# 28pins_schematic.net
KiCad netlist of a schematic drawn in Altium Designer
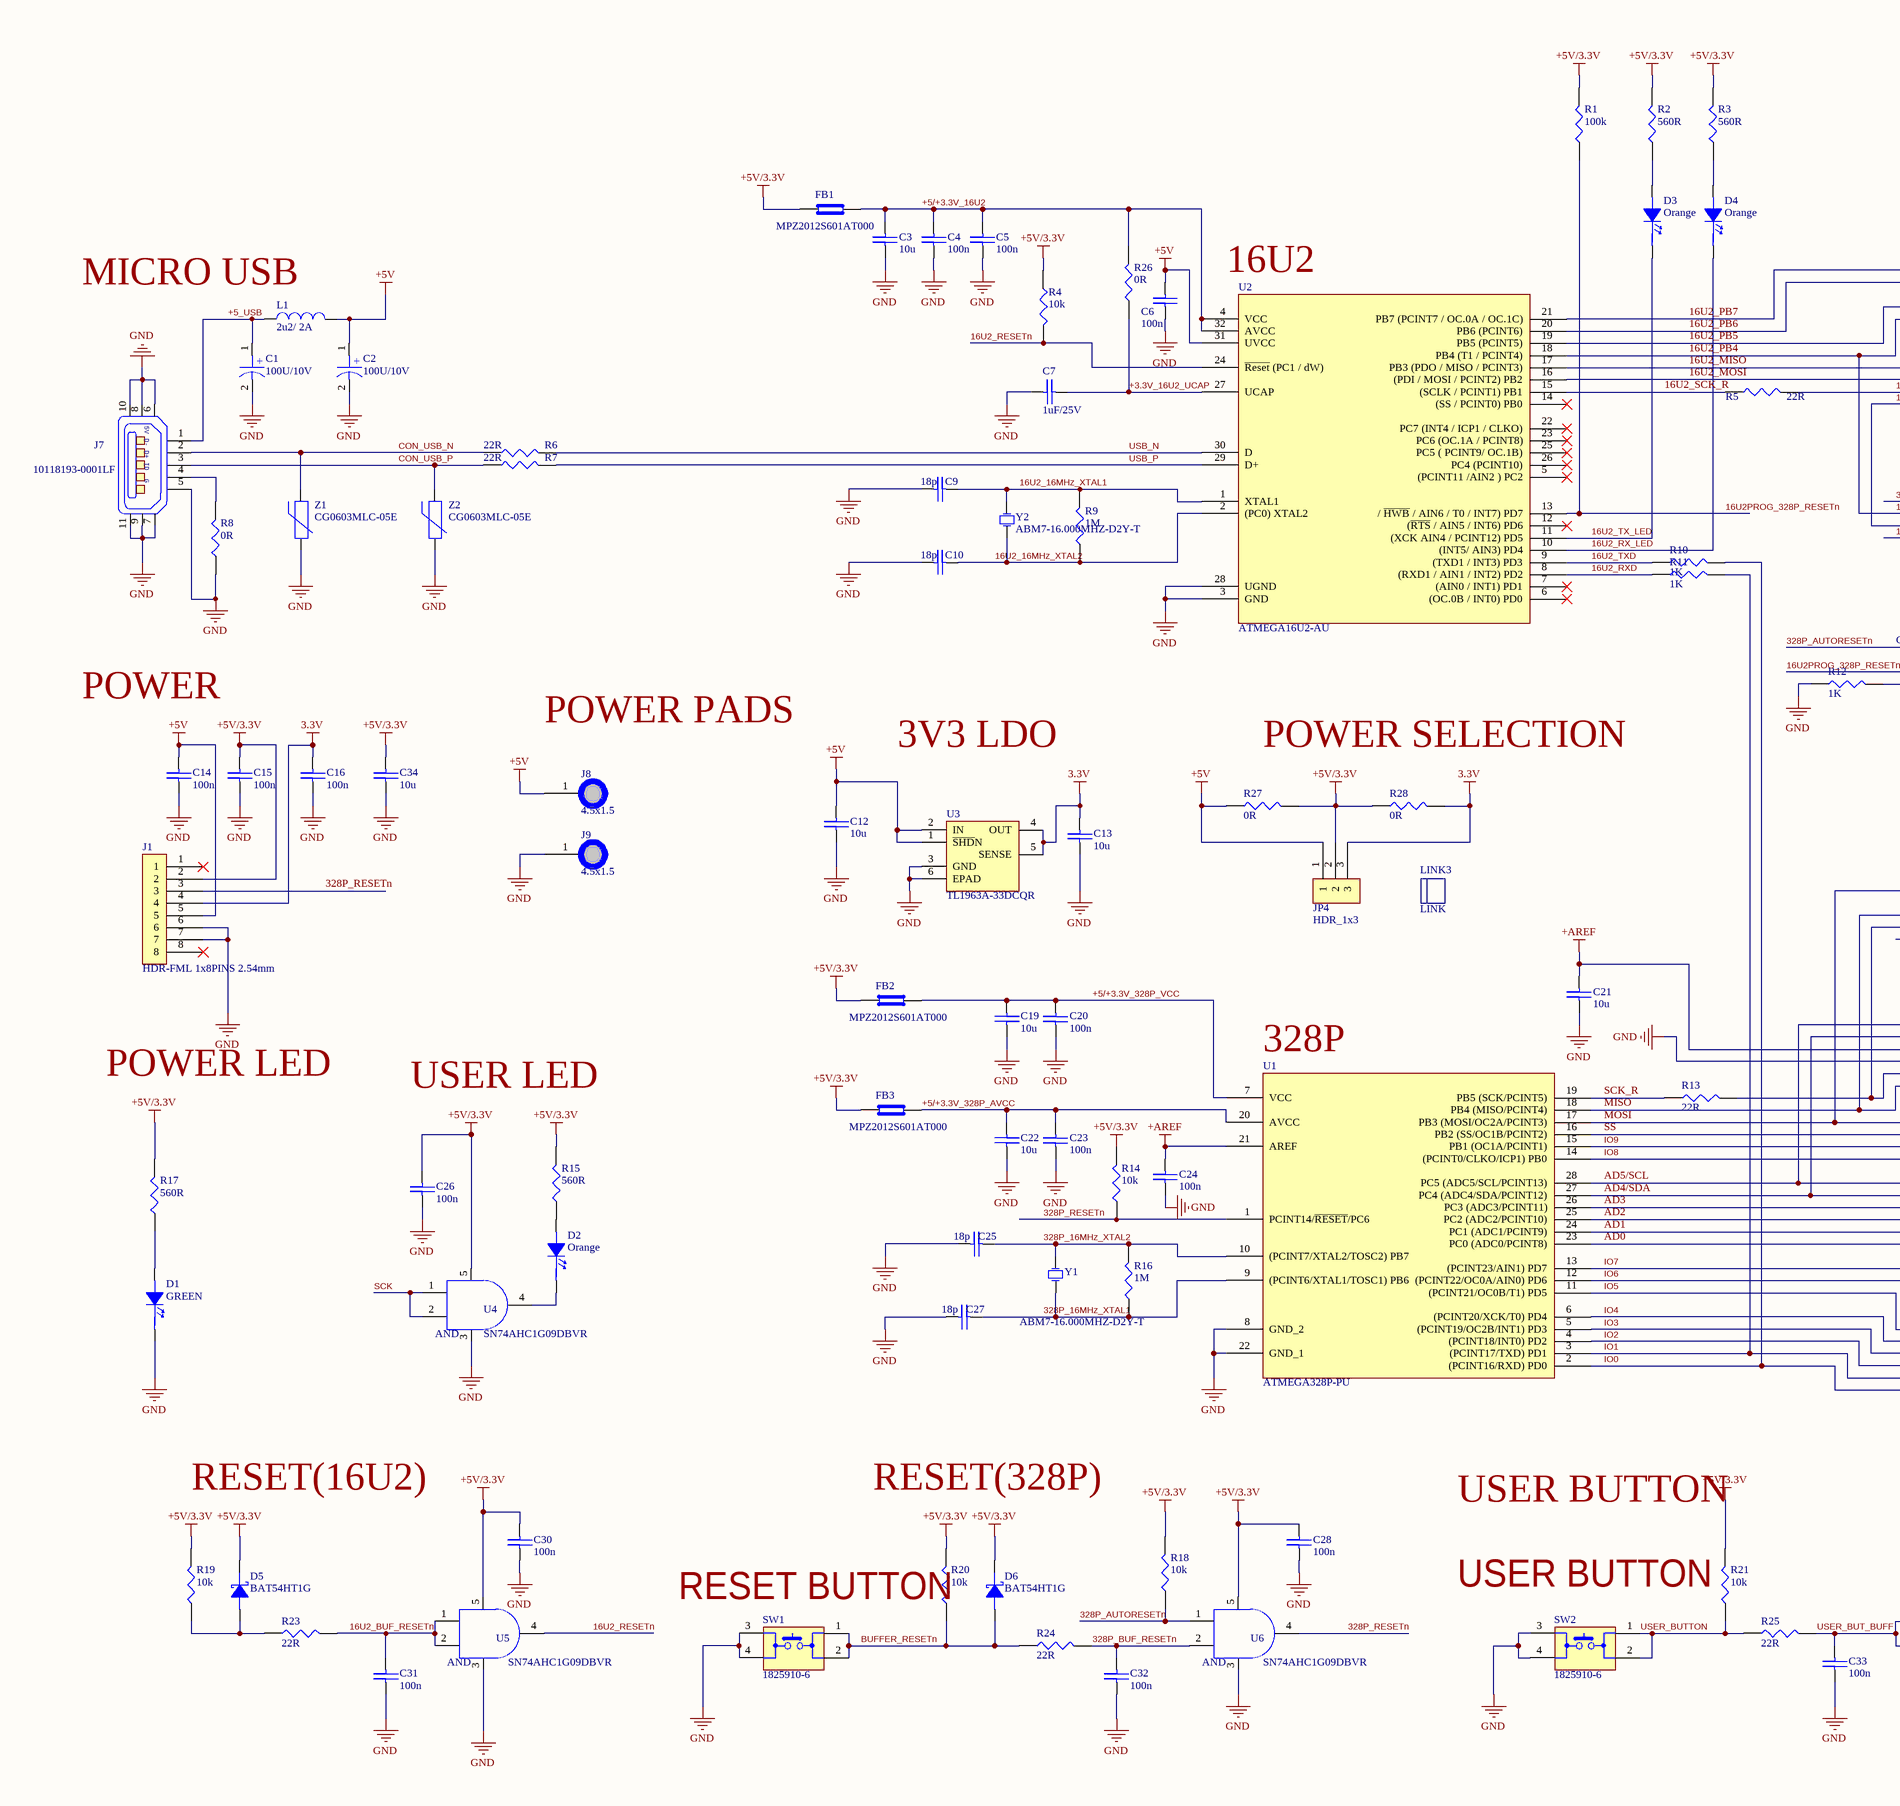
[diagram p0: 28pins_schematic.SchDoc, left]
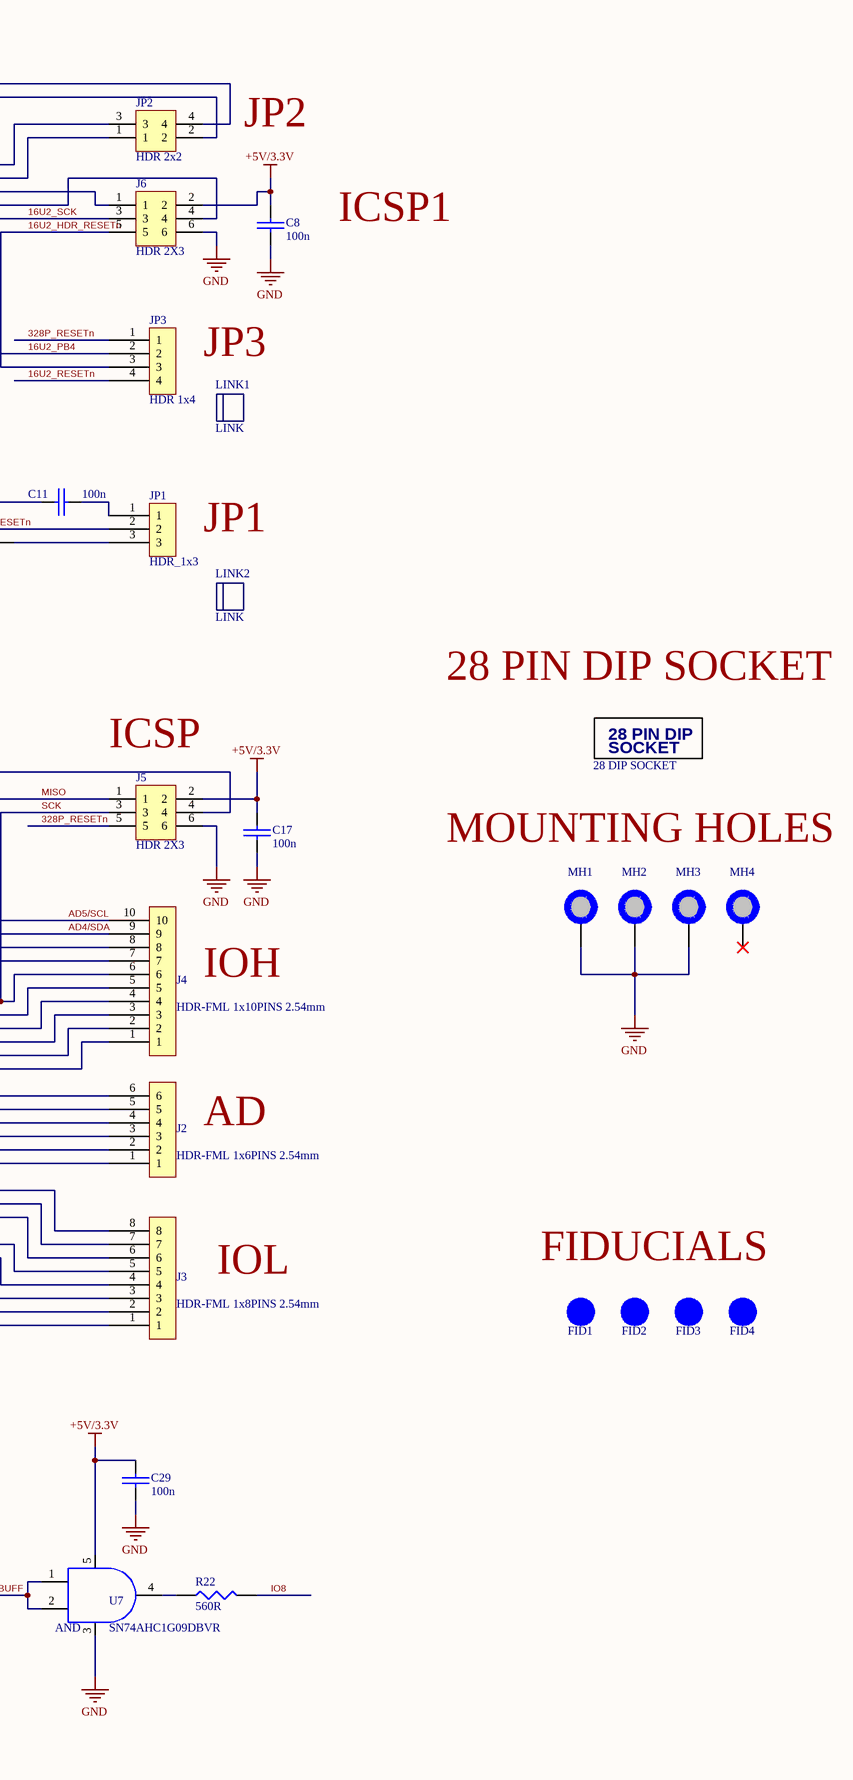
[diagram p1: 28pins_schematic.SchDoc, right]

(export (version "E")
  (design (tool "Eeschema 10.0.6"))
  (components
    (comp (ref "C1")
      (value "100U/10V")
      (footprint "C_ALU_CSIZE")
      (description "Cap Aluminum 100uF 10V 20% (5 X 5.4mm) SMD 50mA 1000 hr 85°C T/R")
      (fields
        (field (name "MANUFACTURER") "Panasonic")
        (field (name "MANUFACTURER PART NUMBER") "EEE-1AA101WR")
      )
      (libsource (lib "28pins_arduino_sch_lib") (part "EEE-1AA101WR"))
    )
    (comp (ref "C2")
      (value "100U/10V")
      (footprint "C_ALU_CSIZE")
      (description "Cap Aluminum 100uF 10V 20% (5 X 5.4mm) SMD 50mA 1000 hr 85°C T/R")
      (fields
        (field (name "MANUFACTURER") "Panasonic")
        (field (name "MANUFACTURER PART NUMBER") "EEE-1AA101WR")
      )
      (libsource (lib "28pins_arduino_sch_lib") (part "EEE-1AA101WR"))
    )
    (comp (ref "C3")
      (value "10u")
      (footprint "C0805 10u/16V")
      (description "Cap Ceramic 22uF 16V X5R 20% SMD 0805 85C Plastic T/R")
      (fields
        (field (name "MANUFACTURER") "TDK")
        (field (name "MANUFACTURER PART NUMBER") "C2012X5R1C226M125AC")
      )
      (libsource (lib "28pins_arduino_sch_lib") (part "C2012X5R1C226M125AC"))
    )
    (comp (ref "C4")
      (value "100n")
      (footprint "C0805")
      (fields
        (field (name "MANUFACTURER") "TDK")
        (field (name "MANUFACTURER PART NUMBER") "C2012X7R1H104K085AA")
        (field (name "TOLERANCE") "10%")
      )
      (libsource (lib "28pins_arduino_sch_lib") (part "C2012X7R1H104K085AA"))
    )
    (comp (ref "C5")
      (value "100n")
      (footprint "C0805")
      (fields
        (field (name "MANUFACTURER") "TDK")
        (field (name "MANUFACTURER PART NUMBER") "C2012X7R1H104K085AA")
        (field (name "TOLERANCE") "10%")
      )
      (libsource (lib "28pins_arduino_sch_lib") (part "C2012X7R1H104K085AA"))
    )
    (comp (ref "C6")
      (value "100n")
      (footprint "C0805")
      (fields
        (field (name "MANUFACTURER") "TDK")
        (field (name "MANUFACTURER PART NUMBER") "C2012X7R1H104K085AA")
        (field (name "TOLERANCE") "10%")
      )
      (libsource (lib "28pins_arduino_sch_lib") (part "C2012X7R1H104K085AA"))
    )
    (comp (ref "C7")
      (value "1uF/25V")
      (footprint "C0805")
      (fields
        (field (name "MANUFACTURER") "TDK")
        (field (name "MANUFACTURER PART NUMBER") "C2012X5R1E105K125AA")
        (field (name "TOLERANCE") "10%")
      )
      (libsource (lib "28pins_arduino_sch_lib") (part "C2012X5R1E105K125AA"))
    )
    (comp (ref "C8")
      (value "100n")
      (footprint "C0805")
      (fields
        (field (name "MANUFACTURER") "TDK")
        (field (name "MANUFACTURER PART NUMBER") "C2012X7R1H104K085AA")
        (field (name "TOLERANCE") "10%")
      )
      (libsource (lib "28pins_arduino_sch_lib") (part "C2012X7R1H104K085AA"))
    )
    (comp (ref "C9")
      (value "18p")
      (footprint "C0805")
      (description "CAP CER 18PF 50V C0G/NP0 0805")
      (fields
        (field (name "MANUFACTURER") "KEMET")
        (field (name "MANUFACTURER PART NUMBER") "C0805C180J5GACTU")
      )
      (libsource (lib "28pins_arduino_sch_lib") (part "C0805C180J5GACTU"))
    )
    (comp (ref "C10")
      (value "18p")
      (footprint "C0805")
      (description "CAP CER 18PF 50V C0G/NP0 0805")
      (fields
        (field (name "MANUFACTURER") "KEMET")
        (field (name "MANUFACTURER PART NUMBER") "C0805C180J5GACTU")
      )
      (libsource (lib "28pins_arduino_sch_lib") (part "C0805C180J5GACTU"))
    )
    (comp (ref "C11")
      (value "100n")
      (footprint "C0805")
      (fields
        (field (name "MANUFACTURER") "TDK")
        (field (name "MANUFACTURER PART NUMBER") "C2012X7R1H104K085AA")
        (field (name "TOLERANCE") "10%")
      )
      (libsource (lib "28pins_arduino_sch_lib") (part "C2012X7R1H104K085AA"))
    )
    (comp (ref "C12")
      (value "10u")
      (footprint "C0805 10u/16V")
      (description "Cap Ceramic 22uF 16V X5R 20% SMD 0805 85C Plastic T/R")
      (fields
        (field (name "MANUFACTURER") "TDK")
        (field (name "MANUFACTURER PART NUMBER") "C2012X5R1C226M125AC")
      )
      (libsource (lib "28pins_arduino_sch_lib") (part "C2012X5R1C226M125AC"))
    )
    (comp (ref "C13")
      (value "10u")
      (footprint "C0805 10u/16V")
      (description "Cap Ceramic 22uF 16V X5R 20% SMD 0805 85C Plastic T/R")
      (fields
        (field (name "MANUFACTURER") "TDK")
        (field (name "MANUFACTURER PART NUMBER") "C2012X5R1C226M125AC")
      )
      (libsource (lib "28pins_arduino_sch_lib") (part "C2012X5R1C226M125AC"))
    )
    (comp (ref "C14")
      (value "100n")
      (footprint "C0805")
      (fields
        (field (name "MANUFACTURER") "TDK")
        (field (name "MANUFACTURER PART NUMBER") "C2012X7R1H104K085AA")
        (field (name "TOLERANCE") "10%")
      )
      (libsource (lib "28pins_arduino_sch_lib") (part "C2012X7R1H104K085AA"))
    )
    (comp (ref "C15")
      (value "100n")
      (footprint "C0805")
      (fields
        (field (name "MANUFACTURER") "TDK")
        (field (name "MANUFACTURER PART NUMBER") "C2012X7R1H104K085AA")
        (field (name "TOLERANCE") "10%")
      )
      (libsource (lib "28pins_arduino_sch_lib") (part "C2012X7R1H104K085AA"))
    )
    (comp (ref "C16")
      (value "100n")
      (footprint "C0805")
      (fields
        (field (name "MANUFACTURER") "TDK")
        (field (name "MANUFACTURER PART NUMBER") "C2012X7R1H104K085AA")
        (field (name "TOLERANCE") "10%")
      )
      (libsource (lib "28pins_arduino_sch_lib") (part "C2012X7R1H104K085AA"))
    )
    (comp (ref "C17")
      (value "100n")
      (footprint "C0805")
      (fields
        (field (name "MANUFACTURER") "TDK")
        (field (name "MANUFACTURER PART NUMBER") "C2012X7R1H104K085AA")
        (field (name "TOLERANCE") "10%")
      )
      (libsource (lib "28pins_arduino_sch_lib") (part "C2012X7R1H104K085AA"))
    )
    (comp (ref "C19")
      (value "10u")
      (footprint "C0805 10u/16V")
      (description "Cap Ceramic 22uF 16V X5R 20% SMD 0805 85C Plastic T/R")
      (fields
        (field (name "MANUFACTURER") "TDK")
        (field (name "MANUFACTURER PART NUMBER") "C2012X5R1C226M125AC")
      )
      (libsource (lib "28pins_arduino_sch_lib") (part "C2012X5R1C226M125AC"))
    )
    (comp (ref "C20")
      (value "100n")
      (footprint "C0805")
      (fields
        (field (name "MANUFACTURER") "TDK")
        (field (name "MANUFACTURER PART NUMBER") "C2012X7R1H104K085AA")
        (field (name "TOLERANCE") "10%")
      )
      (libsource (lib "28pins_arduino_sch_lib") (part "C2012X7R1H104K085AA"))
    )
    (comp (ref "C21")
      (value "10u")
      (footprint "C0805 10u/16V")
      (description "Cap Ceramic 22uF 16V X5R 20% SMD 0805 85C Plastic T/R")
      (fields
        (field (name "MANUFACTURER") "TDK")
        (field (name "MANUFACTURER PART NUMBER") "C2012X5R1C226M125AC")
      )
      (libsource (lib "28pins_arduino_sch_lib") (part "C2012X5R1C226M125AC"))
    )
    (comp (ref "C22")
      (value "10u")
      (footprint "C0805 10u/16V")
      (description "Cap Ceramic 22uF 16V X5R 20% SMD 0805 85C Plastic T/R")
      (fields
        (field (name "MANUFACTURER") "TDK")
        (field (name "MANUFACTURER PART NUMBER") "C2012X5R1C226M125AC")
      )
      (libsource (lib "28pins_arduino_sch_lib") (part "C2012X5R1C226M125AC"))
    )
    (comp (ref "C23")
      (value "100n")
      (footprint "C0805")
      (fields
        (field (name "MANUFACTURER") "TDK")
        (field (name "MANUFACTURER PART NUMBER") "C2012X7R1H104K085AA")
        (field (name "TOLERANCE") "10%")
      )
      (libsource (lib "28pins_arduino_sch_lib") (part "C2012X7R1H104K085AA"))
    )
    (comp (ref "C24")
      (value "100n")
      (footprint "C0805")
      (fields
        (field (name "MANUFACTURER") "TDK")
        (field (name "MANUFACTURER PART NUMBER") "C2012X7R1H104K085AA")
        (field (name "TOLERANCE") "10%")
      )
      (libsource (lib "28pins_arduino_sch_lib") (part "C2012X7R1H104K085AA"))
    )
    (comp (ref "C25")
      (value "18p")
      (footprint "C0805")
      (description "CAP CER 18PF 50V C0G/NP0 0805")
      (fields
        (field (name "MANUFACTURER") "KEMET")
        (field (name "MANUFACTURER PART NUMBER") "C0805C180J5GACTU")
      )
      (libsource (lib "28pins_arduino_sch_lib") (part "C0805C180J5GACTU"))
    )
    (comp (ref "C26")
      (value "100n")
      (footprint "C0805")
      (fields
        (field (name "MANUFACTURER") "TDK")
        (field (name "MANUFACTURER PART NUMBER") "C2012X7R1H104K085AA")
        (field (name "TOLERANCE") "10%")
      )
      (libsource (lib "28pins_arduino_sch_lib") (part "C2012X7R1H104K085AA"))
    )
    (comp (ref "C27")
      (value "18p")
      (footprint "C0805")
      (description "CAP CER 18PF 50V C0G/NP0 0805")
      (fields
        (field (name "MANUFACTURER") "KEMET")
        (field (name "MANUFACTURER PART NUMBER") "C0805C180J5GACTU")
      )
      (libsource (lib "28pins_arduino_sch_lib") (part "C0805C180J5GACTU"))
    )
    (comp (ref "C28")
      (value "100n")
      (footprint "C0805")
      (fields
        (field (name "MANUFACTURER") "TDK")
        (field (name "MANUFACTURER PART NUMBER") "C2012X7R1H104K085AA")
        (field (name "TOLERANCE") "10%")
      )
      (libsource (lib "28pins_arduino_sch_lib") (part "C2012X7R1H104K085AA"))
    )
    (comp (ref "C29")
      (value "100n")
      (footprint "C0805")
      (fields
        (field (name "MANUFACTURER") "TDK")
        (field (name "MANUFACTURER PART NUMBER") "C2012X7R1H104K085AA")
        (field (name "TOLERANCE") "10%")
      )
      (libsource (lib "28pins_arduino_sch_lib") (part "C2012X7R1H104K085AA"))
    )
    (comp (ref "C30")
      (value "100n")
      (footprint "C0805")
      (fields
        (field (name "MANUFACTURER") "TDK")
        (field (name "MANUFACTURER PART NUMBER") "C2012X7R1H104K085AA")
        (field (name "TOLERANCE") "10%")
      )
      (libsource (lib "28pins_arduino_sch_lib") (part "C2012X7R1H104K085AA"))
    )
    (comp (ref "C31")
      (value "100n")
      (footprint "C0805")
      (fields
        (field (name "MANUFACTURER") "TDK")
        (field (name "MANUFACTURER PART NUMBER") "C2012X7R1H104K085AA")
        (field (name "TOLERANCE") "10%")
      )
      (libsource (lib "28pins_arduino_sch_lib") (part "C2012X7R1H104K085AA"))
    )
    (comp (ref "C32")
      (value "100n")
      (footprint "C0805")
      (fields
        (field (name "MANUFACTURER") "TDK")
        (field (name "MANUFACTURER PART NUMBER") "C2012X7R1H104K085AA")
        (field (name "TOLERANCE") "10%")
      )
      (libsource (lib "28pins_arduino_sch_lib") (part "C2012X7R1H104K085AA"))
    )
    (comp (ref "C33")
      (value "100n")
      (footprint "C0805")
      (fields
        (field (name "MANUFACTURER") "TDK")
        (field (name "MANUFACTURER PART NUMBER") "C2012X7R1H104K085AA")
        (field (name "TOLERANCE") "10%")
      )
      (libsource (lib "28pins_arduino_sch_lib") (part "C2012X7R1H104K085AA"))
    )
    (comp (ref "C34")
      (value "10u")
      (footprint "C0805 10u/16V")
      (description "Cap Ceramic 22uF 16V X5R 20% SMD 0805 85C Plastic T/R")
      (fields
        (field (name "MANUFACTURER") "TDK")
        (field (name "MANUFACTURER PART NUMBER") "C2012X5R1C226M125AC")
      )
      (libsource (lib "28pins_arduino_sch_lib") (part "C2012X5R1C226M125AC"))
    )
    (comp (ref "D1")
      (value "GREEN")
      (footprint "LED_0603")
      (description "LED Uni-Color Green 572nm 2-Pin Chip 0603(1608Metric) T/R")
      (fields
        (field (name "MANUFACTURER") "Osram Opto")
        (field (name "MANUFACTURER PART NUMBER") "LGL29K-G2J1-24-Z")
      )
      (libsource (lib "28pins_arduino_sch_lib") (part "LGL29K-G2J1-24-Z"))
    )
    (comp (ref "D2")
      (value "Orange")
      (footprint "LED_0603")
      (description "OSRAM - LO L29K-H2K1-24-Z - SMARTLED 0603 ORANGE")
      (fields
        (field (name "MANUFACTURER") "Osram Opto")
        (field (name "MANUFACTURER PART NUMBER") "LOL29K-H2K1-24-Z")
      )
      (libsource (lib "28pins_arduino_sch_lib") (part "LOL29K-H2K1-24-Z"))
    )
    (comp (ref "D3")
      (value "Orange")
      (footprint "LED_0603")
      (description "OSRAM - LO L29K-H2K1-24-Z - SMARTLED 0603 ORANGE")
      (fields
        (field (name "MANUFACTURER") "Osram Opto")
        (field (name "MANUFACTURER PART NUMBER") "LOL29K-H2K1-24-Z")
      )
      (libsource (lib "28pins_arduino_sch_lib") (part "LOL29K-H2K1-24-Z"))
    )
    (comp (ref "D4")
      (value "Orange")
      (footprint "LED_0603")
      (description "OSRAM - LO L29K-H2K1-24-Z - SMARTLED 0603 ORANGE")
      (fields
        (field (name "MANUFACTURER") "Osram Opto")
        (field (name "MANUFACTURER PART NUMBER") "LOL29K-H2K1-24-Z")
      )
      (libsource (lib "28pins_arduino_sch_lib") (part "LOL29K-H2K1-24-Z"))
    )
    (comp (ref "D5")
      (value "BAT54HT1G")
      (footprint "SOD323")
      (description "Small Signal Schottky Diode, Single, 30 V, 200 mA, 800 mV, 600 mA, 150 C ;RoHS Compliant: Yes")
      (fields (field (name "MANUFACTURER") "ON Semiconductor / Fairchild"))
      (libsource (lib "28pins_arduino_sch_lib") (part "BAT54HT1G"))
    )
    (comp (ref "D6")
      (value "BAT54HT1G")
      (footprint "SOD323")
      (description "Small Signal Schottky Diode, Single, 30 V, 200 mA, 800 mV, 600 mA, 150 C ;RoHS Compliant: Yes")
      (fields (field (name "MANUFACTURER") "ON Semiconductor / Fairchild"))
      (libsource (lib "28pins_arduino_sch_lib") (part "BAT54HT1G"))
    )
    (comp (ref "FB1")
      (value "MPZ2012S601AT000")
      (footprint "C0805")
      (description "FERRITE BEAD 600 OHM 0805 1LN")
      (fields (field (name "MANUFACTURER") "TDK"))
      (libsource (lib "28pins_arduino_sch_lib") (part "MPZ2012S601AT000"))
    )
    (comp (ref "FB2")
      (value "MPZ2012S601AT000")
      (footprint "C0805")
      (description "FERRITE BEAD 600 OHM 0805 1LN")
      (fields (field (name "MANUFACTURER") "TDK"))
      (libsource (lib "28pins_arduino_sch_lib") (part "MPZ2012S601AT000"))
    )
    (comp (ref "FB3")
      (value "MPZ2012S601AT000")
      (footprint "C0805")
      (description "FERRITE BEAD 600 OHM 0805 1LN")
      (fields (field (name "MANUFACTURER") "TDK"))
      (libsource (lib "28pins_arduino_sch_lib") (part "MPZ2012S601AT000"))
    )
    (comp (ref "FID1")
      (value "FID_1MM")
      (footprint "FID_40x120")
      (description "fiducial 40mil diameter,120mil mask")
      (libsource (lib "28pins_arduino_sch_lib") (part "FID_1MM"))
    )
    (comp (ref "FID2")
      (value "FID_1MM")
      (footprint "FID_40x120")
      (description "fiducial 40mil diameter,120mil mask")
      (libsource (lib "28pins_arduino_sch_lib") (part "FID_1MM"))
    )
    (comp (ref "FID3")
      (value "FID_1MM")
      (footprint "FID_40x120")
      (description "fiducial 40mil diameter,120mil mask")
      (libsource (lib "28pins_arduino_sch_lib") (part "FID_1MM"))
    )
    (comp (ref "FID4")
      (value "FID_1MM")
      (footprint "FID_40x120")
      (description "fiducial 40mil diameter,120mil mask")
      (libsource (lib "28pins_arduino_sch_lib") (part "FID_1MM"))
    )
    (comp (ref "J1")
      (value "HDR-FML 1x8PINS 2.54mm")
      (footprint "Hdr_Fml_1x8_2.54mm")
      (description "2.54mm (0.1\") Pitch SIL Vertical PC Tail Socket Assembly, selective gold + tin, 8 contacts")
      (fields (field (name "MANUFACTURER") "Harwin") (field (name "MANUFACTURER PART NUMBER") "M20-7820842"))
      (libsource (lib "") (part "M20-7820842_1"))
    )
    (comp (ref "J2")
      (value "HDR-FML 1x6PINS 2.54mm")
      (footprint "Hdr_Fml_1x6_2.54mm")
      (description "06-WAY SIL VERT SOCKET L/FREE")
      (fields (field (name "MANUFACTURER") "Harwin") (field (name "MANUFACTURER PART NUMBER") "M20-7820646"))
      (libsource (lib "28pins_arduino_sch_lib") (part "M20-7820646"))
    )
    (comp (ref "J3")
      (value "HDR-FML 1x8PINS 2.54mm")
      (footprint "Hdr_Fml_1x8_2.54mm")
      (description "2.54mm (0.1\") Pitch SIL Vertical PC Tail Socket Assembly, selective gold + tin, 8 contacts")
      (fields (field (name "MANUFACTURER") "Harwin") (field (name "MANUFACTURER PART NUMBER") "M20-7820842"))
      (libsource (lib "28pins_arduino_sch_lib") (part "M20-7820842"))
    )
    (comp (ref "J4")
      (value "HDR-FML 1x10PINS 2.54mm")
      (footprint "Hdr_Fml_1x10_2.54mm")
      (fields (field (name "MANUFACTURER") "Harwin") (field (name "MANUFACTURER PART NUMBER") "M20-7821046"))
      (libsource (lib "28pins_arduino_sch_lib") (part "M20-7821046"))
    )
    (comp (ref "J5")
      (value "HDR 2X3")
      (footprint "HDR 2x3_2.54mm")
      (description "CONN HEADER 6POS .100 STR 30AU")
      (fields
        (field (name "MANUFACTURER") "Amphenol FCI")
        (field (name "MANUFACTURER PART NUMBER") "67997-106HLF")
      )
      (libsource (lib "28pins_arduino_sch_lib") (part "67997-106HLF"))
    )
    (comp (ref "J6")
      (value "HDR 2X3")
      (footprint "HDR 2x3_2.54mm")
      (description "CONN HEADER 6POS .100 STR 30AU")
      (fields
        (field (name "MANUFACTURER") "Amphenol FCI")
        (field (name "MANUFACTURER PART NUMBER") "67997-106HLF")
      )
      (libsource (lib "28pins_arduino_sch_lib") (part "67997-106HLF"))
    )
    (comp (ref "J7")
      (value "10118193-0001LF")
      (footprint "10118193-0001LF")
      (description "CONN USB MICRO B RECPT SMT R/A")
      (fields (field (name "MANUFACTURER") "Amphenol FCI"))
      (libsource (lib "28pins_arduino_sch_lib") (part "10118193-0001LF"))
    )
    (comp (ref "J8")
      (value "4.5x1.5")
      (footprint "PAD_WITH_HOLE_4.5MMx1.5MM")
      (description "pad with a hole 4.5mmx1.5mm")
      (libsource (lib "28pins_arduino_sch_lib") (part "PAD_WITH_HOLE_4MMx1.5MM"))
    )
    (comp (ref "J9")
      (value "4.5x1.5")
      (footprint "PAD_WITH_HOLE_4.5MMx1.5MM")
      (description "pad with a hole 4.5mmx1.5mm")
      (libsource (lib "28pins_arduino_sch_lib") (part "PAD_WITH_HOLE_4MMx1.5MM"))
    )
    (comp (ref "JP1")
      (value "HDR_1x3")
      (footprint "Hdr_Fml_1x3_2.54mm")
      (description "Conn Unshrouded Header HDR 3 POS 2.54mm Solder ST Thru-Hole Bulk")
      (fields
        (field (name "MANUFACTURER") "Amphenol FCI")
        (field (name "MANUFACTURER PART NUMBER") "68000-103HLF")
      )
      (libsource (lib "") (part "68000-103HLF_1"))
    )
    (comp (ref "JP2")
      (value "HDR 2x2")
      (footprint "HDR 2x2_2.54mm")
      (description "CONN HEADER VERT 4POS 2.54MM")
      (fields
        (field (name "MANUFACTURER") "Amphenol FCI")
        (field (name "MANUFACTURER PART NUMBER") "68602-204HLF")
      )
      (libsource (lib "28pins_arduino_sch_lib") (part "68602-204HLF"))
    )
    (comp (ref "JP3")
      (value "HDR 1x4")
      (footprint "Hdr_Fml_1x4_2.54mm")
      (description "CONN HEADER VERT 4POS 2.54MM")
      (fields
        (field (name "MANUFACTURER") "Amphenol FCI")
        (field (name "MANUFACTURER PART NUMBER") "68001-204HLF")
      )
      (libsource (lib "28pins_arduino_sch_lib") (part "68001-204HLF"))
    )
    (comp (ref "JP4")
      (value "HDR_1x3")
      (footprint "Hdr_Fml_1x3_2.54mm")
      (description "Conn Unshrouded Header HDR 3 POS 2.54mm Solder ST Thru-Hole Bulk")
      (fields
        (field (name "MANUFACTURER") "Amphenol FCI")
        (field (name "MANUFACTURER PART NUMBER") "68000-103HLF")
      )
      (libsource (lib "28pins_arduino_sch_lib") (part "68000-103HLF"))
    )
    (comp (ref "L1")
      (value "2u2/ 2A")
      (footprint "C1210_IND")
      (description "FIXED IND 2.2UH 2A 80 MOHM SMD")
      (fields
        (field (name "MANUFACTURER") "KEMET")
        (field (name "MANUFACTURER PART NUMBER") "L1210R2R2MDWIT")
      )
      (libsource (lib "28pins_arduino_sch_lib") (part "L1210R2R2MDWIT"))
    )
    (comp (ref "LINK1")
      (value "LINK")
      (description "CONN JUMPER SHORTING .100\" GOLD")
      (fields
        (field (name "MANUFACTURER") "Sullins")
        (field (name "MANUFACTURER PART NUMBER") "QPC02SXGN-RC")
      )
      (libsource (lib "28pins_arduino_sch_lib") (part "QPC02SXGN-RC"))
    )
    (comp (ref "LINK2")
      (value "LINK")
      (description "CONN JUMPER SHORTING .100\" GOLD")
      (fields
        (field (name "MANUFACTURER") "Sullins")
        (field (name "MANUFACTURER PART NUMBER") "QPC02SXGN-RC")
      )
      (libsource (lib "28pins_arduino_sch_lib") (part "QPC02SXGN-RC"))
    )
    (comp (ref "LINK3")
      (value "LINK")
      (description "CONN JUMPER SHORTING .100\" GOLD")
      (fields
        (field (name "MANUFACTURER") "Sullins")
        (field (name "MANUFACTURER PART NUMBER") "QPC02SXGN-RC")
      )
      (libsource (lib "28pins_arduino_sch_lib") (part "QPC02SXGN-RC"))
    )
    (comp (ref "MH1")
      (value "MH_7.4MMCX3.2MMD")
      (footprint "MH_7.4MMx3.2MM")
      (description "Mounting hole 7.4mm diameter, 3.2mm drill")
      (libsource (lib "28pins_arduino_sch_lib") (part "MH_7.4MMx3.2MM"))
    )
    (comp (ref "MH2")
      (value "MH_7.4MMCX3.2MMD")
      (footprint "MH_7.4MMx3.2MM")
      (description "Mounting hole 7.4mm diameter, 3.2mm drill")
      (libsource (lib "28pins_arduino_sch_lib") (part "MH_7.4MMx3.2MM"))
    )
    (comp (ref "MH3")
      (value "MH_7.4MMCX3.2MMD")
      (footprint "MH_7.4MMx3.2MM")
      (description "Mounting hole 7.4mm diameter, 3.2mm drill")
      (libsource (lib "28pins_arduino_sch_lib") (part "MH_7.4MMx3.2MM"))
    )
    (comp (ref "MH4")
      (value "MH_7.4MMNP_3.2MMD")
      (footprint "MH_7.4MMD_3.2MM_NON_COPPER_NPTH")
      (description "hole 7.4 diamerter non copper, 3.2 drill NPTH")
      (libsource (lib "28pins_arduino_sch_lib") (part "MH_7.4MMNP_3.2MMD"))
    )
    (comp (ref "R1")
      (value "100k")
      (footprint "R0805")
      (description "YAGEO         RC0805FR-07100KL            RES, THICK FILM, 100K, 1%, 0.125W, 0805, REEL")
      (fields
        (field (name "MANUFACTURER") "Yageo")
        (field (name "MANUFACTURER PART NUMBER") "RC0805FR-07100KL")
      )
      (libsource (lib "28pins_arduino_sch_lib") (part "RC0805FR-07100KL"))
    )
    (comp (ref "R2")
      (value "560R")
      (footprint "R0805")
      (description "Surface Mount Thick Film Resistor, RC Series, 560 ohm, 125 mW, - 1%, 150 V, 0805 [2012 Metric]")
      (fields
        (field (name "MANUFACTURER") "Yageo")
        (field (name "MANUFACTURER PART NUMBER") "RC0805FR-07560RL")
      )
      (libsource (lib "28pins_arduino_sch_lib") (part "RC0805FR-07560RL"))
    )
    (comp (ref "R3")
      (value "560R")
      (footprint "R0805")
      (description "Surface Mount Thick Film Resistor, RC Series, 560 ohm, 125 mW, - 1%, 150 V, 0805 [2012 Metric]")
      (fields
        (field (name "MANUFACTURER") "Yageo")
        (field (name "MANUFACTURER PART NUMBER") "RC0805FR-07560RL")
      )
      (libsource (lib "28pins_arduino_sch_lib") (part "RC0805FR-07560RL"))
    )
    (comp (ref "R4")
      (value "10k")
      (footprint "R0805")
      (description "RES SMD 10K OHM 1% 1/8W 0805")
      (fields
        (field (name "MANUFACTURER") "Yageo")
        (field (name "MANUFACTURER PART NUMBER") "RC0805FR-0710KL")
      )
      (libsource (lib "28pins_arduino_sch_lib") (part "RC0805FR-0710KL"))
    )
    (comp (ref "R5")
      (value "22R")
      (footprint "R0805")
      (description "RES SMD 22 OHM 1% 1/8W 0805")
      (fields
        (field (name "MANUFACTURER") "Yageo")
        (field (name "MANUFACTURER PART NUMBER") "RC0805FR-0722RL")
      )
      (libsource (lib "28pins_arduino_sch_lib") (part "RC0805FR-0722RL"))
    )
    (comp (ref "R6")
      (value "22R")
      (footprint "R0805")
      (description "RES SMD 22 OHM 1% 1/8W 0805")
      (fields
        (field (name "MANUFACTURER") "Yageo")
        (field (name "MANUFACTURER PART NUMBER") "RC0805FR-0722RL")
      )
      (libsource (lib "28pins_arduino_sch_lib") (part "RC0805FR-0722RL"))
    )
    (comp (ref "R7")
      (value "22R")
      (footprint "R0805")
      (description "RES SMD 22 OHM 1% 1/8W 0805")
      (fields
        (field (name "MANUFACTURER") "Yageo")
        (field (name "MANUFACTURER PART NUMBER") "RC0805FR-0722RL")
      )
      (libsource (lib "28pins_arduino_sch_lib") (part "RC0805FR-0722RL"))
    )
    (comp (ref "R8")
      (value "0R")
      (footprint "R0805")
      (description "Res Thick Film 0805 0 Ohm Epoxy Pad SMD T/R")
      (fields
        (field (name "MANUFACTURER") "Yageo")
        (field (name "MANUFACTURER PART NUMBER") "RC0805FR-070RL")
      )
      (libsource (lib "28pins_arduino_sch_lib") (part "RC0805FR-070RL"))
    )
    (comp (ref "R9")
      (value "1M")
      (footprint "R0805")
      (description "RES SMD 1M OHM 1% 1/8W 0805")
      (fields
        (field (name "MANUFACTURER") "Yageo")
        (field (name "MANUFACTURER PART NUMBER") "RC0805FR-071ML")
      )
      (libsource (lib "28pins_arduino_sch_lib") (part "RC0805FR-071ML"))
    )
    (comp (ref "R10")
      (value "1K")
      (footprint "R0805")
      (fields
        (field (name "MANUFACTURER") "Yageo")
        (field (name "MANUFACTURER PART NUMBER") "RC0805FR-071KL")
        (field (name "TOLERANCE") "1%")
      )
      (libsource (lib "28pins_arduino_sch_lib") (part "RC0805FR-071KL"))
    )
    (comp (ref "R11")
      (value "1K")
      (footprint "R0805")
      (fields
        (field (name "MANUFACTURER") "Yageo")
        (field (name "MANUFACTURER PART NUMBER") "RC0805FR-071KL")
        (field (name "TOLERANCE") "1%")
      )
      (libsource (lib "28pins_arduino_sch_lib") (part "RC0805FR-071KL"))
    )
    (comp (ref "R12")
      (value "1K")
      (footprint "R0805")
      (fields
        (field (name "MANUFACTURER") "Yageo")
        (field (name "MANUFACTURER PART NUMBER") "RC0805FR-071KL")
        (field (name "TOLERANCE") "1%")
      )
      (libsource (lib "28pins_arduino_sch_lib") (part "RC0805FR-071KL"))
    )
    (comp (ref "R13")
      (value "22R")
      (footprint "R0805")
      (description "RES SMD 22 OHM 1% 1/8W 0805")
      (fields
        (field (name "MANUFACTURER") "Yageo")
        (field (name "MANUFACTURER PART NUMBER") "RC0805FR-0722RL")
      )
      (libsource (lib "28pins_arduino_sch_lib") (part "RC0805FR-0722RL"))
    )
    (comp (ref "R14")
      (value "10k")
      (footprint "R0805")
      (description "RES SMD 10K OHM 1% 1/8W 0805")
      (fields
        (field (name "MANUFACTURER") "Yageo")
        (field (name "MANUFACTURER PART NUMBER") "RC0805FR-0710KL")
      )
      (libsource (lib "28pins_arduino_sch_lib") (part "RC0805FR-0710KL"))
    )
    (comp (ref "R15")
      (value "560R")
      (footprint "R0805")
      (description "Surface Mount Thick Film Resistor, RC Series, 560 ohm, 125 mW, - 1%, 150 V, 0805 [2012 Metric]")
      (fields
        (field (name "MANUFACTURER") "Yageo")
        (field (name "MANUFACTURER PART NUMBER") "RC0805FR-07560RL")
      )
      (libsource (lib "28pins_arduino_sch_lib") (part "RC0805FR-07560RL"))
    )
    (comp (ref "R16")
      (value "1M")
      (footprint "R0805")
      (description "RES SMD 1M OHM 1% 1/8W 0805")
      (fields
        (field (name "MANUFACTURER") "Yageo")
        (field (name "MANUFACTURER PART NUMBER") "RC0805FR-071ML")
      )
      (libsource (lib "28pins_arduino_sch_lib") (part "RC0805FR-071ML"))
    )
    (comp (ref "R17")
      (value "560R")
      (footprint "R0805")
      (description "Surface Mount Thick Film Resistor, RC Series, 560 ohm, 125 mW, - 1%, 150 V, 0805 [2012 Metric]")
      (fields
        (field (name "MANUFACTURER") "Yageo")
        (field (name "MANUFACTURER PART NUMBER") "RC0805FR-07560RL")
      )
      (libsource (lib "28pins_arduino_sch_lib") (part "RC0805FR-07560RL"))
    )
    (comp (ref "R18")
      (value "10k")
      (footprint "R0805")
      (description "RES SMD 10K OHM 1% 1/8W 0805")
      (fields
        (field (name "MANUFACTURER") "Yageo")
        (field (name "MANUFACTURER PART NUMBER") "RC0805FR-0710KL")
      )
      (libsource (lib "28pins_arduino_sch_lib") (part "RC0805FR-0710KL"))
    )
    (comp (ref "R19")
      (value "10k")
      (footprint "R0805")
      (description "RES SMD 10K OHM 1% 1/8W 0805")
      (fields
        (field (name "MANUFACTURER") "Yageo")
        (field (name "MANUFACTURER PART NUMBER") "RC0805FR-0710KL")
      )
      (libsource (lib "28pins_arduino_sch_lib") (part "RC0805FR-0710KL"))
    )
    (comp (ref "R20")
      (value "10k")
      (footprint "R0805")
      (description "RES SMD 10K OHM 1% 1/8W 0805")
      (fields
        (field (name "MANUFACTURER") "Yageo")
        (field (name "MANUFACTURER PART NUMBER") "RC0805FR-0710KL")
      )
      (libsource (lib "28pins_arduino_sch_lib") (part "RC0805FR-0710KL"))
    )
    (comp (ref "R21")
      (value "10k")
      (footprint "R0805")
      (description "RES SMD 10K OHM 1% 1/8W 0805")
      (fields
        (field (name "MANUFACTURER") "Yageo")
        (field (name "MANUFACTURER PART NUMBER") "RC0805FR-0710KL")
      )
      (libsource (lib "28pins_arduino_sch_lib") (part "RC0805FR-0710KL"))
    )
    (comp (ref "R22")
      (value "560R")
      (footprint "R0805")
      (description "Surface Mount Thick Film Resistor, RC Series, 560 ohm, 125 mW, - 1%, 150 V, 0805 [2012 Metric]")
      (fields
        (field (name "MANUFACTURER") "Yageo")
        (field (name "MANUFACTURER PART NUMBER") "RC0805FR-07560RL")
      )
      (libsource (lib "28pins_arduino_sch_lib") (part "RC0805FR-07560RL"))
    )
    (comp (ref "R23")
      (value "22R")
      (footprint "R0805")
      (description "RES SMD 22 OHM 1% 1/8W 0805")
      (fields
        (field (name "MANUFACTURER") "Yageo")
        (field (name "MANUFACTURER PART NUMBER") "RC0805FR-0722RL")
      )
      (libsource (lib "28pins_arduino_sch_lib") (part "RC0805FR-0722RL"))
    )
    (comp (ref "R24")
      (value "22R")
      (footprint "R0805")
      (description "RES SMD 22 OHM 1% 1/8W 0805")
      (fields
        (field (name "MANUFACTURER") "Yageo")
        (field (name "MANUFACTURER PART NUMBER") "RC0805FR-0722RL")
      )
      (libsource (lib "28pins_arduino_sch_lib") (part "RC0805FR-0722RL"))
    )
    (comp (ref "R25")
      (value "22R")
      (footprint "R0805")
      (description "RES SMD 22 OHM 1% 1/8W 0805")
      (fields
        (field (name "MANUFACTURER") "Yageo")
        (field (name "MANUFACTURER PART NUMBER") "RC0805FR-0722RL")
      )
      (libsource (lib "28pins_arduino_sch_lib") (part "RC0805FR-0722RL"))
    )
    (comp (ref "R26")
      (value "0R")
      (footprint "R0805")
      (description "Res Thick Film 0805 0 Ohm Epoxy Pad SMD T/R")
      (fields
        (field (name "MANUFACTURER") "Yageo")
        (field (name "MANUFACTURER PART NUMBER") "RC0805FR-070RL")
      )
      (libsource (lib "28pins_arduino_sch_lib") (part "RC0805FR-070RL"))
    )
    (comp (ref "R27")
      (value "0R")
      (footprint "R0805")
      (description "Res Thick Film 0805 0 Ohm Epoxy Pad SMD T/R")
      (fields
        (field (name "MANUFACTURER") "Yageo")
        (field (name "MANUFACTURER PART NUMBER") "RC0805FR-070RL")
      )
      (libsource (lib "28pins_arduino_sch_lib") (part "RC0805FR-070RL"))
    )
    (comp (ref "R28")
      (value "0R")
      (footprint "R0805")
      (description "Res Thick Film 0805 0 Ohm Epoxy Pad SMD T/R")
      (fields
        (field (name "MANUFACTURER") "Yageo")
        (field (name "MANUFACTURER PART NUMBER") "RC0805FR-070RL")
      )
      (libsource (lib "28pins_arduino_sch_lib") (part "RC0805FR-070RL"))
    )
    (comp (ref "SCKT for U1")
      (value "28 DIP SOCKET")
      (footprint "28 DIP 7.62mm SCKT")
      (description "CONN IC DIP SOCKET 28POS TIN")
      (fields (field (name "MANUFACTURER") "3M") (field (name "MANUFACTURER PART NUMBER") "4828-3004-CP"))
      (libsource (lib "28pins_arduino_sch_lib") (part "4828-3004-CP"))
    )
    (comp (ref "SW1")
      (value "1825910-6")
      (footprint "1825910-6")
      (description "SWITCH TACTILE SPST-NO 0.05A 24V")
      (fields (field (name "MANUFACTURER") "TE Connectivity Alcoswitch"))
      (libsource (lib "28pins_arduino_sch_lib") (part "1825910-6"))
    )
    (comp (ref "SW2")
      (value "1825910-6")
      (footprint "1825910-6")
      (description "SWITCH TACTILE SPST-NO 0.05A 24V")
      (fields (field (name "MANUFACTURER") "TE Connectivity Alcoswitch"))
      (libsource (lib "28pins_arduino_sch_lib") (part "1825910-6"))
    )
    (comp (ref "U1")
      (value "ATMEGA328P-PU")
      (footprint "28pin_dip")
      (description "ATMEGA328P-PU; 8 bit Microcontroller AVR 20MHz 1; 32kb Flash; 2kb RAM; I2C SPI 2")
      (fields (field (name "MANUFACTURER") "Microchip / Atmel"))
      (libsource (lib "28pins_arduino_sch_lib") (part "ATMEGA328P-PU"))
    )
    (comp (ref "U2")
      (value "ATMEGA16U2-AU")
      (footprint "TQFP32")
      (description "MICROCHIP - ATMEGA16U2-AU - MCU, 8BIT, MEGAAVR, 16MHZ, TQFP-32")
      (fields (field (name "MANUFACTURER") "Microchip / Atmel"))
      (libsource (lib "28pins_arduino_sch_lib") (part "ATMEGA16U2-AU"))
    )
    (comp (ref "U3")
      (value "TL1963A-33DCQR")
      (footprint "DCQ(PDS-G6)")
      (description "IC REG LINEAR 3.3V 1.5A SOT223-6")
      (fields (field (name "MANUFACTURER") "Texas Instruments"))
      (libsource (lib "28pins_arduino_sch_lib") (part "TL1963A-33DCQR"))
    )
    (comp (ref "U4")
      (value "SN74AHC1G09DBVR")
      (footprint "DBV_SOT_23")
      (description "TEXAS INSTRUMENTS - SN74AHC1G09DBVR - AND Gate, 74AHC1G09, 2 Input, 2 V to 5.5 V, SOT-23-5")
      (fields (field (name "MANUFACTURER") "Texas Instruments"))
      (libsource (lib "28pins_arduino_sch_lib") (part "SN74AHC1G09DBVR"))
    )
    (comp (ref "U5")
      (value "SN74AHC1G09DBVR")
      (footprint "DBV_SOT_23")
      (description "TEXAS INSTRUMENTS - SN74AHC1G09DBVR - AND Gate, 74AHC1G09, 2 Input, 2 V to 5.5 V, SOT-23-5")
      (fields (field (name "MANUFACTURER") "Texas Instruments"))
      (libsource (lib "28pins_arduino_sch_lib") (part "SN74AHC1G09DBVR"))
    )
    (comp (ref "U6")
      (value "SN74AHC1G09DBVR")
      (footprint "DBV_SOT_23")
      (description "TEXAS INSTRUMENTS - SN74AHC1G09DBVR - AND Gate, 74AHC1G09, 2 Input, 2 V to 5.5 V, SOT-23-5")
      (fields (field (name "MANUFACTURER") "Texas Instruments"))
      (libsource (lib "28pins_arduino_sch_lib") (part "SN74AHC1G09DBVR"))
    )
    (comp (ref "U7")
      (value "SN74AHC1G09DBVR")
      (footprint "DBV_SOT_23")
      (description "TEXAS INSTRUMENTS - SN74AHC1G09DBVR - AND Gate, 74AHC1G09, 2 Input, 2 V to 5.5 V, SOT-23-5")
      (fields (field (name "MANUFACTURER") "Texas Instruments"))
      (libsource (lib "28pins_arduino_sch_lib") (part "SN74AHC1G09DBVR"))
    )
    (comp (ref "Y1")
      (value "ABM7-16.000MHZ-D2Y-T")
      (footprint "ABM_V1_BIG")
      (description "CRYSTAL 16.0000MHZ 18PF SMD")
      (fields (field (name "MANUFACTURER") "Abracon") (field (name "TOLERANCE") "20ppm"))
      (libsource (lib "28pins_arduino_sch_lib") (part "ABM7-16.000MHZ-D2Y-T"))
    )
    (comp (ref "Y2")
      (value "ABM7-16.000MHZ-D2Y-T")
      (footprint "ABM_V1_BIG")
      (description "CRYSTAL 16.0000MHZ 18PF SMD")
      (fields (field (name "MANUFACTURER") "Abracon") (field (name "TOLERANCE") "20ppm"))
      (libsource (lib "28pins_arduino_sch_lib") (part "ABM7-16.000MHZ-D2Y-T"))
    )
    (comp (ref "Z1")
      (value "CG0603MLC-05E")
      (footprint "R0603")
      (description "VARISTOR 0603")
      (fields (field (name "MANUFACTURER") "Bourns") (field (name "VOLTAGE") "5V"))
      (libsource (lib "28pins_arduino_sch_lib") (part "CG0603MLC-05E"))
    )
    (comp (ref "Z2")
      (value "CG0603MLC-05E")
      (footprint "R0603")
      (description "VARISTOR 0603")
      (fields (field (name "MANUFACTURER") "Bourns") (field (name "VOLTAGE") "5V"))
      (libsource (lib "28pins_arduino_sch_lib") (part "CG0603MLC-05E"))
    )
  )
  (nets
    (net (code "1") (name "+5V") (class "Default")
      (node (ref "C12") (pin "2") (pinfunction "2_2") (pintype "passive"))
      (node (ref "C14") (pin "2") (pinfunction "2_2") (pintype "passive"))
      (node (ref "C2") (pin "1") (pinfunction "1_1") (pintype "passive"))
      (node (ref "C6") (pin "2") (pinfunction "2_2") (pintype "passive"))
      (node (ref "J1") (pin "5") (pinfunction "5_5") (pintype "passive"))
      (node (ref "J8") (pin "1") (pinfunction "1_1") (pintype "passive"))
      (node (ref "JP4") (pin "1") (pinfunction "1_1") (pintype "passive"))
      (node (ref "L1") (pin "2") (pinfunction "2_2") (pintype "passive"))
      (node (ref "R27") (pin "1") (pinfunction "1_1") (pintype "passive"))
      (node (ref "U2") (pin "31") (pinfunction "UVCC_31") (pintype "passive"))
      (node (ref "U3") (pin "1") (pinfunction "~{SHD}N_1") (pintype "passive"))
      (node (ref "U3") (pin "2") (pinfunction "IN_2") (pintype "passive"))
    )
    (net (code "2") (name "+5V{slash}3.3V") (class "Default")
      (node (ref "C15") (pin "2") (pinfunction "2_2") (pintype "passive"))
      (node (ref "C17") (pin "2") (pinfunction "2_2") (pintype "passive"))
      (node (ref "C26") (pin "2") (pinfunction "2_2") (pintype "passive"))
      (node (ref "C28") (pin "2") (pinfunction "2_2") (pintype "passive"))
      (node (ref "C29") (pin "2") (pinfunction "2_2") (pintype "passive"))
      (node (ref "C30") (pin "2") (pinfunction "2_2") (pintype "passive"))
      (node (ref "C34") (pin "2") (pinfunction "2_2") (pintype "passive"))
      (node (ref "C8") (pin "2") (pinfunction "2_2") (pintype "passive"))
      (node (ref "D5") (pin "1") (pinfunction "Cathode_1") (pintype "passive"))
      (node (ref "D6") (pin "1") (pinfunction "Cathode_1") (pintype "passive"))
      (node (ref "FB1") (pin "1") (pinfunction "1_1") (pintype "passive"))
      (node (ref "FB2") (pin "1") (pinfunction "1_1") (pintype "passive"))
      (node (ref "FB3") (pin "1") (pinfunction "1_1") (pintype "passive"))
      (node (ref "J1") (pin "2") (pinfunction "2_2") (pintype "passive"))
      (node (ref "J5") (pin "2") (pinfunction "2_2") (pintype "passive"))
      (node (ref "J6") (pin "2") (pinfunction "2_2") (pintype "passive"))
      (node (ref "JP4") (pin "2") (pinfunction "2_2") (pintype "passive"))
      (node (ref "R1") (pin "2") (pinfunction "2_2") (pintype "passive"))
      (node (ref "R14") (pin "2") (pinfunction "2_2") (pintype "passive"))
      (node (ref "R15") (pin "2") (pinfunction "2_2") (pintype "passive"))
      (node (ref "R17") (pin "2") (pinfunction "2_2") (pintype "passive"))
      (node (ref "R18") (pin "2") (pinfunction "2_2") (pintype "passive"))
      (node (ref "R19") (pin "2") (pinfunction "2_2") (pintype "passive"))
      (node (ref "R2") (pin "2") (pinfunction "2_2") (pintype "passive"))
      (node (ref "R20") (pin "2") (pinfunction "2_2") (pintype "passive"))
      (node (ref "R21") (pin "2") (pinfunction "2_2") (pintype "passive"))
      (node (ref "R27") (pin "2") (pinfunction "2_2") (pintype "passive"))
      (node (ref "R28") (pin "1") (pinfunction "1_1") (pintype "passive"))
      (node (ref "R3") (pin "2") (pinfunction "2_2") (pintype "passive"))
      (node (ref "R4") (pin "1") (pinfunction "1_1") (pintype "passive"))
      (node (ref "U4") (pin "5") (pinfunction "5_5") (pintype "passive"))
      (node (ref "U5") (pin "5") (pinfunction "5_5") (pintype "passive"))
      (node (ref "U6") (pin "5") (pinfunction "5_5") (pintype "passive"))
      (node (ref "U7") (pin "5") (pinfunction "5_5") (pintype "passive"))
    )
    (net (code "3") (name "+AREF") (class "Default")
      (node (ref "C21") (pin "2") (pinfunction "2_2") (pintype "passive"))
      (node (ref "C24") (pin "2") (pinfunction "2_2") (pintype "passive"))
      (node (ref "J4") (pin "8") (pinfunction "8_8") (pintype "passive"))
      (node (ref "U1") (pin "21") (pinfunction "AREF_21") (pintype "passive"))
    )
    (net (code "4") (name "/+3.3V_16U2_UCAP") (class "Default")
      (node (ref "C7") (pin "2") (pinfunction "2_2") (pintype "passive"))
      (node (ref "R26") (pin "1") (pinfunction "1_1") (pintype "passive"))
      (node (ref "U2") (pin "27") (pinfunction "UCAP_27") (pintype "passive"))
    )
    (net (code "5") (name "/+5_USB") (class "Default")
      (node (ref "C1") (pin "1") (pinfunction "1_1") (pintype "passive"))
      (node (ref "J7") (pin "1") (pinfunction "1_1") (pintype "passive"))
      (node (ref "L1") (pin "1") (pinfunction "1_1") (pintype "passive"))
    )
    (net (code "6") (name "/+5{slash}+3.3V_16U2") (class "Default")
      (node (ref "C3") (pin "2") (pinfunction "2_2") (pintype "passive"))
      (node (ref "C4") (pin "2") (pinfunction "2_2") (pintype "passive"))
      (node (ref "C5") (pin "2") (pinfunction "2_2") (pintype "passive"))
      (node (ref "FB1") (pin "2") (pinfunction "2_2") (pintype "passive"))
      (node (ref "R26") (pin "2") (pinfunction "2_2") (pintype "passive"))
      (node (ref "U2") (pin "32") (pinfunction "AVCC_32") (pintype "passive"))
      (node (ref "U2") (pin "4") (pinfunction "VCC_4") (pintype "passive"))
    )
    (net (code "7") (name "/+5{slash}+3.3V_328P_AVCC") (class "Default")
      (node (ref "C22") (pin "1") (pinfunction "1_1") (pintype "passive"))
      (node (ref "C23") (pin "2") (pinfunction "2_2") (pintype "passive"))
      (node (ref "FB3") (pin "2") (pinfunction "2_2") (pintype "passive"))
      (node (ref "U1") (pin "20") (pinfunction "AVCC_20") (pintype "passive"))
    )
    (net (code "8") (name "/+5{slash}+3.3V_328P_VCC") (class "Default")
      (node (ref "C19") (pin "1") (pinfunction "1_1") (pintype "passive"))
      (node (ref "C20") (pin "2") (pinfunction "2_2") (pintype "passive"))
      (node (ref "FB2") (pin "2") (pinfunction "2_2") (pintype "passive"))
      (node (ref "U1") (pin "7") (pinfunction "VCC_7") (pintype "passive"))
    )
    (net (code "9") (name "/16U2PROG_328P_RESETn") (class "Default")
      (node (ref "JP1") (pin "2") (pinfunction "2_2") (pintype "passive"))
      (node (ref "R1") (pin "1") (pinfunction "1_1") (pintype "passive"))
      (node (ref "U2") (pin "13") (pinfunction "/_~{HWB}_/_AIN6_/_T0_/_INT7)_PD7_13") (pintype "passive"))
    )
    (net (code "10") (name "/16U2_16MHz_XTAL1") (class "Default")
      (node (ref "C9") (pin "2") (pinfunction "2_2") (pintype "passive"))
      (node (ref "R9") (pin "2") (pinfunction "2_2") (pintype "passive"))
      (node (ref "U2") (pin "1") (pinfunction "XTAL1_1") (pintype "passive"))
      (node (ref "Y2") (pin "2") (pinfunction "2_2") (pintype "passive"))
    )
    (net (code "11") (name "/16U2_16MHz_XTAL2") (class "Default")
      (node (ref "C10") (pin "2") (pinfunction "2_2") (pintype "passive"))
      (node (ref "R9") (pin "1") (pinfunction "1_1") (pintype "passive"))
      (node (ref "U2") (pin "2") (pinfunction "(PC0)_XTAL2_2") (pintype "passive"))
      (node (ref "Y2") (pin "1") (pinfunction "1_1") (pintype "passive"))
    )
    (net (code "12") (name "/16U2_BUF_RESETn") (class "Default")
      (node (ref "C31") (pin "2") (pinfunction "2_2") (pintype "passive"))
      (node (ref "R23") (pin "2") (pinfunction "2_2") (pintype "passive"))
      (node (ref "U5") (pin "1") (pinfunction "1_1") (pintype "passive"))
      (node (ref "U5") (pin "2") (pinfunction "2_2") (pintype "passive"))
    )
    (net (code "13") (name "/16U2_HDR_RESETn") (class "Default")
      (node (ref "J6") (pin "5") (pinfunction "5_5") (pintype "passive"))
      (node (ref "JP3") (pin "3") (pinfunction "3_3") (pintype "passive"))
    )
    (net (code "14") (name "/16U2_MISO") (class "Default")
      (node (ref "J6") (pin "1") (pinfunction "1_1") (pintype "passive"))
      (node (ref "U2") (pin "17") (pinfunction "PB3_(PDO_/_MISO_/_PCINT3)_17") (pintype "passive"))
    )
    (net (code "15") (name "/16U2_MOSI") (class "Default")
      (node (ref "J6") (pin "4") (pinfunction "4_4") (pintype "passive"))
      (node (ref "U2") (pin "16") (pinfunction "(PDI_/_MOSI_/_PCINT2)_PB2_16") (pintype "passive"))
    )
    (net (code "16") (name "/16U2_PB4") (class "Default")
      (node (ref "JP2") (pin "1") (pinfunction "1_1") (pintype "passive"))
      (node (ref "JP3") (pin "2") (pinfunction "2_2") (pintype "passive"))
      (node (ref "U2") (pin "18") (pinfunction "PB4_(T1_/_PCINT4)_18") (pintype "passive"))
    )
    (net (code "17") (name "/16U2_PB5") (class "Default")
      (node (ref "JP2") (pin "3") (pinfunction "3_3") (pintype "passive"))
      (node (ref "U2") (pin "19") (pinfunction "PB5_(PCINT5)_19") (pintype "passive"))
    )
    (net (code "18") (name "/16U2_PB6") (class "Default")
      (node (ref "JP2") (pin "2") (pinfunction "2_2") (pintype "passive"))
      (node (ref "U2") (pin "20") (pinfunction "PB6_(PCINT6)_20") (pintype "passive"))
    )
    (net (code "19") (name "/16U2_PB7") (class "Default")
      (node (ref "JP2") (pin "4") (pinfunction "4_4") (pintype "passive"))
      (node (ref "U2") (pin "21") (pinfunction "PB7_(PCINT7_/_OC.0A_/_OC.1C)_21") (pintype "passive"))
    )
    (net (code "20") (name "/16U2_RESETn") (class "Default")
      (node (ref "JP3") (pin "4") (pinfunction "4_4") (pintype "passive"))
      (node (ref "R4") (pin "2") (pinfunction "2_2") (pintype "passive"))
      (node (ref "U2") (pin "24") (pinfunction "~{Reset}_(PC1_/_dW)_24") (pintype "passive"))
      (node (ref "U5") (pin "4") (pinfunction "4_4") (pintype "passive"))
    )
    (net (code "21") (name "/16U2_RXD") (class "Default")
      (node (ref "R11") (pin "1") (pintype "passive"))
      (node (ref "U2") (pin "8") (pinfunction "(RXD1_/_AIN1_/_INT2)_PD2_8") (pintype "passive"))
    )
    (net (code "22") (name "/16U2_RX_LED") (class "Default")
      (node (ref "D4") (pin "1") (pinfunction "Cathode_1") (pintype "passive"))
      (node (ref "U2") (pin "10") (pinfunction "(INT5/_AIN3)_PD4_10") (pintype "passive"))
    )
    (net (code "23") (name "/16U2_SCK") (class "Default")
      (node (ref "J6") (pin "3") (pinfunction "3_3") (pintype "passive"))
      (node (ref "R5") (pin "2") (pinfunction "2_2") (pintype "passive"))
    )
    (net (code "24") (name "/16U2_SCK_R") (class "Default")
      (node (ref "R5") (pin "1") (pinfunction "1_1") (pintype "passive"))
      (node (ref "U2") (pin "15") (pinfunction "(SCLK_/_PCINT1)_PB1_15") (pintype "passive"))
    )
    (net (code "25") (name "/16U2_TXD") (class "Default")
      (node (ref "R10") (pin "1") (pintype "passive"))
      (node (ref "U2") (pin "9") (pinfunction "(TXD1_/_INT3)_PD3_9") (pintype "passive"))
    )
    (net (code "26") (name "/16U2_TX_LED") (class "Default")
      (node (ref "D3") (pin "1") (pinfunction "Cathode_1") (pintype "passive"))
      (node (ref "U2") (pin "11") (pinfunction "(XCK_AIN4_/_PCINT12)_PD5_11") (pintype "passive"))
    )
    (net (code "27") (name "/328P_16MHz_XTAL1") (class "Default")
      (node (ref "C27") (pin "2") (pinfunction "2_2") (pintype "passive"))
      (node (ref "R16") (pin "1") (pinfunction "1_1") (pintype "passive"))
      (node (ref "U1") (pin "9") (pinfunction "(PCINT6/XTAL1/TOSC1)_PB6_9") (pintype "passive"))
      (node (ref "Y1") (pin "1") (pinfunction "1_1") (pintype "passive"))
    )
    (net (code "28") (name "/328P_16MHz_XTAL2") (class "Default")
      (node (ref "C25") (pin "2") (pinfunction "2_2") (pintype "passive"))
      (node (ref "R16") (pin "2") (pinfunction "2_2") (pintype "passive"))
      (node (ref "U1") (pin "10") (pinfunction "(PCINT7/XTAL2/TOSC2)_PB7_10") (pintype "passive"))
      (node (ref "Y1") (pin "2") (pinfunction "2_2") (pintype "passive"))
    )
    (net (code "29") (name "/328P_AUTORESETn") (class "Default")
      (node (ref "C11") (pin "1") (pinfunction "1_1") (pintype "passive"))
      (node (ref "R18") (pin "1") (pinfunction "1_1") (pintype "passive"))
      (node (ref "U6") (pin "1") (pinfunction "1_1") (pintype "passive"))
    )
    (net (code "30") (name "/328P_BUF_RESETn") (class "Default")
      (node (ref "C32") (pin "2") (pinfunction "2_2") (pintype "passive"))
      (node (ref "R24") (pin "2") (pinfunction "2_2") (pintype "passive"))
      (node (ref "U6") (pin "2") (pinfunction "2_2") (pintype "passive"))
    )
    (net (code "31") (name "/328P_RESETn") (class "Default")
      (node (ref "J1") (pin "3") (pinfunction "3_3") (pintype "passive"))
      (node (ref "J5") (pin "5") (pinfunction "5_5") (pintype "passive"))
      (node (ref "JP3") (pin "1") (pinfunction "1_1") (pintype "passive"))
      (node (ref "R14") (pin "1") (pinfunction "1_1") (pintype "passive"))
      (node (ref "U1") (pin "1") (pinfunction "PCINT14/~{RESET}/PC6_1") (pintype "passive"))
      (node (ref "U6") (pin "4") (pinfunction "4_4") (pintype "passive"))
    )
    (net (code "32") (name "/AD0") (class "Default")
      (node (ref "J2") (pin "1") (pinfunction "1_1") (pintype "passive"))
      (node (ref "U1") (pin "23") (pinfunction "PC0_(ADC0/PCINT8)_23") (pintype "passive"))
    )
    (net (code "33") (name "/AD1") (class "Default")
      (node (ref "J2") (pin "2") (pinfunction "2_2") (pintype "passive"))
      (node (ref "U1") (pin "24") (pinfunction "PC1_(ADC1/PCINT9)_24") (pintype "passive"))
    )
    (net (code "34") (name "/AD2") (class "Default")
      (node (ref "J2") (pin "3") (pinfunction "3_3") (pintype "passive"))
      (node (ref "U1") (pin "25") (pinfunction "PC2_(ADC2/PCINT10)_25") (pintype "passive"))
    )
    (net (code "35") (name "/AD3") (class "Default")
      (node (ref "J2") (pin "4") (pinfunction "4_4") (pintype "passive"))
      (node (ref "U1") (pin "26") (pinfunction "PC3_(ADC3/PCINT11)_26") (pintype "passive"))
    )
    (net (code "36") (name "/AD4{slash}SDA") (class "Default")
      (node (ref "J2") (pin "5") (pinfunction "5_5") (pintype "passive"))
      (node (ref "J4") (pin "9") (pinfunction "9_9") (pintype "passive"))
      (node (ref "U1") (pin "27") (pinfunction "PC4_(ADC4/SDA/PCINT12)_27") (pintype "passive"))
    )
    (net (code "37") (name "/AD5{slash}SCL") (class "Default")
      (node (ref "J2") (pin "6") (pinfunction "6_6") (pintype "passive"))
      (node (ref "J4") (pin "10") (pinfunction "10_10") (pintype "passive"))
      (node (ref "U1") (pin "28") (pinfunction "PC5_(ADC5/SCL/PCINT13)_28") (pintype "passive"))
    )
    (net (code "38") (name "/BUFFER_RESETn") (class "Default")
      (node (ref "D6") (pin "2") (pinfunction "Anode_2") (pintype "passive"))
      (node (ref "R20") (pin "1") (pinfunction "1_1") (pintype "passive"))
      (node (ref "R24") (pin "1") (pinfunction "1_1") (pintype "passive"))
      (node (ref "SW1") (pin "1") (pinfunction "1_1") (pintype "passive"))
      (node (ref "SW1") (pin "2") (pinfunction "2_2") (pintype "passive"))
    )
    (net (code "39") (name "/CON_USB_N") (class "Default")
      (node (ref "J7") (pin "2") (pinfunction "2_2") (pintype "passive"))
      (node (ref "R6") (pin "1") (pinfunction "1_1") (pintype "passive"))
      (node (ref "Z1") (pin "2") (pinfunction "2_2") (pintype "passive"))
    )
    (net (code "40") (name "/CON_USB_P") (class "Default")
      (node (ref "J7") (pin "3") (pinfunction "3_3") (pintype "passive"))
      (node (ref "R7") (pin "1") (pinfunction "1_1") (pintype "passive"))
      (node (ref "Z2") (pin "2") (pinfunction "2_2") (pintype "passive"))
    )
    (net (code "41") (name "/IO0") (class "Default")
      (node (ref "J3") (pin "1") (pinfunction "1_1") (pintype "passive"))
      (node (ref "R10") (pin "2") (pinfunction "2_2") (pintype "passive"))
      (node (ref "U1") (pin "2") (pinfunction "(PCINT16/RXD)_PD0_2") (pintype "passive"))
    )
    (net (code "42") (name "/IO1") (class "Default")
      (node (ref "J3") (pin "2") (pinfunction "2_2") (pintype "passive"))
      (node (ref "R11") (pin "2") (pinfunction "2_2") (pintype "passive"))
      (node (ref "U1") (pin "3") (pinfunction "(PCINT17/TXD)_PD1_3") (pintype "passive"))
    )
    (net (code "43") (name "/IO2") (class "Default")
      (node (ref "J3") (pin "3") (pinfunction "3_3") (pintype "passive"))
      (node (ref "U1") (pin "4") (pinfunction "(PCINT18/INT0)_PD2_4") (pintype "passive"))
    )
    (net (code "44") (name "/IO3") (class "Default")
      (node (ref "J3") (pin "4") (pinfunction "4_4") (pintype "passive"))
      (node (ref "U1") (pin "5") (pinfunction "(PCINT19/OC2B/INT1)_PD3_5") (pintype "passive"))
    )
    (net (code "45") (name "/IO4") (class "Default")
      (node (ref "J3") (pin "5") (pinfunction "5_5") (pintype "passive"))
      (node (ref "U1") (pin "6") (pinfunction "(PCINT20/XCK/T0)_PD4_6") (pintype "passive"))
    )
    (net (code "46") (name "/IO5") (class "Default")
      (node (ref "J3") (pin "6") (pinfunction "6_6") (pintype "passive"))
      (node (ref "U1") (pin "11") (pinfunction "(PCINT21/OC0B/T1)_PD5_11") (pintype "passive"))
    )
    (net (code "47") (name "/IO6") (class "Default")
      (node (ref "J3") (pin "7") (pinfunction "7_7") (pintype "passive"))
      (node (ref "U1") (pin "12") (pinfunction "(PCINT22/OC0A/AIN0)_PD6_12") (pintype "passive"))
    )
    (net (code "48") (name "/IO7") (class "Default")
      (node (ref "J3") (pin "8") (pinfunction "8_8") (pintype "passive"))
      (node (ref "U1") (pin "13") (pinfunction "(PCINT23/AIN1)_PD7_13") (pintype "passive"))
    )
    (net (code "49") (name "/IO8") (class "Default")
      (node (ref "J4") (pin "1") (pinfunction "1_1") (pintype "passive"))
      (node (ref "R22") (pin "2") (pinfunction "2_2") (pintype "passive"))
      (node (ref "U1") (pin "14") (pinfunction "(PCINT0/CLKO/ICP1)_PB0_14") (pintype "passive"))
    )
    (net (code "50") (name "/IO9") (class "Default")
      (node (ref "J4") (pin "2") (pinfunction "2_2") (pintype "passive"))
      (node (ref "U1") (pin "15") (pinfunction "PB1_(OC1A/PCINT1)_15") (pintype "passive"))
    )
    (net (code "51") (name "/MISO") (class "Default")
      (node (ref "J4") (pin "5") (pinfunction "5_5") (pintype "passive"))
      (node (ref "J5") (pin "1") (pinfunction "1_1") (pintype "passive"))
      (node (ref "U1") (pin "18") (pinfunction "PB4_(MISO/PCINT4)_18") (pintype "passive"))
    )
    (net (code "52") (name "/MOSI") (class "Default")
      (node (ref "J4") (pin "4") (pinfunction "4_4") (pintype "passive"))
      (node (ref "J5") (pin "4") (pinfunction "4_4") (pintype "passive"))
      (node (ref "U1") (pin "17") (pinfunction "PB3_(MOSI/OC2A/PCINT3)_17") (pintype "passive"))
    )
    (net (code "53") (name "/SCK") (class "Default")
      (node (ref "J4") (pin "6") (pinfunction "6_6") (pintype "passive"))
      (node (ref "J5") (pin "3") (pinfunction "3_3") (pintype "passive"))
      (node (ref "R13") (pin "2") (pinfunction "2_2") (pintype "passive"))
      (node (ref "U4") (pin "1") (pinfunction "1_1") (pintype "passive"))
      (node (ref "U4") (pin "2") (pinfunction "2_2") (pintype "passive"))
    )
    (net (code "54") (name "/SCK_R") (class "Default")
      (node (ref "R13") (pin "1") (pinfunction "1_1") (pintype "passive"))
      (node (ref "U1") (pin "19") (pinfunction "PB5_(SCK/PCINT5)_19") (pintype "passive"))
    )
    (net (code "55") (name "/SS") (class "Default")
      (node (ref "J4") (pin "3") (pinfunction "3_3") (pintype "passive"))
      (node (ref "U1") (pin "16") (pinfunction "PB2_(SS/OC1B/PCINT2)_16") (pintype "passive"))
    )
    (net (code "56") (name "/USB_N") (class "Default")
      (node (ref "R6") (pin "2") (pinfunction "2_2") (pintype "passive"))
      (node (ref "U2") (pin "30") (pinfunction "D_30") (pintype "passive"))
    )
    (net (code "57") (name "/USB_P") (class "Default")
      (node (ref "R7") (pin "2") (pinfunction "2_2") (pintype "passive"))
      (node (ref "U2") (pin "29") (pinfunction "D+_29") (pintype "passive"))
    )
    (net (code "58") (name "/USER_BUTTON") (class "Default")
      (node (ref "R21") (pin "1") (pinfunction "1_1") (pintype "passive"))
      (node (ref "R25") (pin "1") (pinfunction "1_1") (pintype "passive"))
      (node (ref "SW2") (pin "1") (pinfunction "1_1") (pintype "passive"))
      (node (ref "SW2") (pin "2") (pinfunction "2_2") (pintype "passive"))
    )
    (net (code "59") (name "/USER_BUT_BUFF") (class "Default")
      (node (ref "C33") (pin "2") (pinfunction "2_2") (pintype "passive"))
      (node (ref "R25") (pin "2") (pinfunction "2_2") (pintype "passive"))
      (node (ref "U7") (pin "1") (pinfunction "1_1") (pintype "passive"))
      (node (ref "U7") (pin "2") (pinfunction "2_2") (pintype "passive"))
    )
    (net (code "60") (name "3.3V") (class "Default")
      (node (ref "C13") (pin "2") (pinfunction "2_2") (pintype "passive"))
      (node (ref "C16") (pin "2") (pinfunction "2_2") (pintype "passive"))
      (node (ref "J1") (pin "4") (pinfunction "4_4") (pintype "passive"))
      (node (ref "JP4") (pin "3") (pinfunction "3_3") (pintype "passive"))
      (node (ref "R28") (pin "2") (pinfunction "2_2") (pintype "passive"))
      (node (ref "U3") (pin "4") (pinfunction "OUT_4") (pintype "passive"))
      (node (ref "U3") (pin "5") (pinfunction "SENSE_5") (pintype "passive"))
    )
    (net (code "61") (name "GND") (class "Default")
      (node (ref "C1") (pin "2") (pinfunction "2_2") (pintype "passive"))
      (node (ref "C10") (pin "1") (pinfunction "1_1") (pintype "passive"))
      (node (ref "C12") (pin "1") (pinfunction "1_1") (pintype "passive"))
      (node (ref "C13") (pin "1") (pinfunction "1_1") (pintype "passive"))
      (node (ref "C14") (pin "1") (pinfunction "1_1") (pintype "passive"))
      (node (ref "C15") (pin "1") (pinfunction "1_1") (pintype "passive"))
      (node (ref "C16") (pin "1") (pinfunction "1_1") (pintype "passive"))
      (node (ref "C17") (pin "1") (pinfunction "1_1") (pintype "passive"))
      (node (ref "C19") (pin "2") (pinfunction "2_2") (pintype "passive"))
      (node (ref "C2") (pin "2") (pinfunction "2_2") (pintype "passive"))
      (node (ref "C20") (pin "1") (pinfunction "1_1") (pintype "passive"))
      (node (ref "C21") (pin "1") (pinfunction "1_1") (pintype "passive"))
      (node (ref "C22") (pin "2") (pinfunction "2_2") (pintype "passive"))
      (node (ref "C23") (pin "1") (pinfunction "1_1") (pintype "passive"))
      (node (ref "C24") (pin "1") (pinfunction "1_1") (pintype "passive"))
      (node (ref "C25") (pin "1") (pinfunction "1_1") (pintype "passive"))
      (node (ref "C26") (pin "1") (pinfunction "1_1") (pintype "passive"))
      (node (ref "C27") (pin "1") (pinfunction "1_1") (pintype "passive"))
      (node (ref "C28") (pin "1") (pinfunction "1_1") (pintype "passive"))
      (node (ref "C29") (pin "1") (pinfunction "1_1") (pintype "passive"))
      (node (ref "C3") (pin "1") (pinfunction "1_1") (pintype "passive"))
      (node (ref "C30") (pin "1") (pinfunction "1_1") (pintype "passive"))
      (node (ref "C31") (pin "1") (pinfunction "1_1") (pintype "passive"))
      (node (ref "C32") (pin "1") (pinfunction "1_1") (pintype "passive"))
      (node (ref "C33") (pin "1") (pinfunction "1_1") (pintype "passive"))
      (node (ref "C34") (pin "1") (pinfunction "1_1") (pintype "passive"))
      (node (ref "C4") (pin "1") (pinfunction "1_1") (pintype "passive"))
      (node (ref "C5") (pin "1") (pinfunction "1_1") (pintype "passive"))
      (node (ref "C6") (pin "1") (pinfunction "1_1") (pintype "passive"))
      (node (ref "C7") (pin "1") (pinfunction "1_1") (pintype "passive"))
      (node (ref "C8") (pin "1") (pinfunction "1_1") (pintype "passive"))
      (node (ref "C9") (pin "1") (pinfunction "1_1") (pintype "passive"))
      (node (ref "D1") (pin "1") (pinfunction "Cathode_1") (pintype "passive"))
      (node (ref "J1") (pin "6") (pinfunction "6_6") (pintype "passive"))
      (node (ref "J1") (pin "7") (pinfunction "7_7") (pintype "passive"))
      (node (ref "J4") (pin "7") (pinfunction "7_7") (pintype "passive"))
      (node (ref "J5") (pin "6") (pinfunction "6_6") (pintype "passive"))
      (node (ref "J6") (pin "6") (pinfunction "6_6") (pintype "passive"))
      (node (ref "J7") (pin "10") (pinfunction "10_10") (pintype "passive"))
      (node (ref "J7") (pin "11") (pinfunction "11_11") (pintype "passive"))
      (node (ref "J7") (pin "5") (pinfunction "5_5") (pintype "passive"))
      (node (ref "J7") (pin "6") (pinfunction "6_6") (pintype "passive"))
      (node (ref "J7") (pin "7") (pinfunction "7_7") (pintype "passive"))
      (node (ref "J7") (pin "8") (pinfunction "8_8") (pintype "passive"))
      (node (ref "J7") (pin "9") (pinfunction "9_9") (pintype "passive"))
      (node (ref "J9") (pin "1") (pinfunction "1_1") (pintype "passive"))
      (node (ref "MH1") (pin "1") (pinfunction "1_1") (pintype "passive"))
      (node (ref "MH2") (pin "1") (pinfunction "1_1") (pintype "passive"))
      (node (ref "MH3") (pin "1") (pinfunction "1_1") (pintype "passive"))
      (node (ref "R12") (pin "1") (pintype "passive"))
      (node (ref "R8") (pin "1") (pinfunction "1_1") (pintype "passive"))
      (node (ref "SW1") (pin "3") (pinfunction "3_3") (pintype "passive"))
      (node (ref "SW1") (pin "4") (pinfunction "4_4") (pintype "passive"))
      (node (ref "SW2") (pin "3") (pinfunction "3_3") (pintype "passive"))
      (node (ref "SW2") (pin "4") (pinfunction "4_4") (pintype "passive"))
      (node (ref "U1") (pin "22") (pinfunction "GND_1_22") (pintype "passive"))
      (node (ref "U1") (pin "8") (pinfunction "GND_2_8") (pintype "passive"))
      (node (ref "U2") (pin "28") (pinfunction "UGND_28") (pintype "passive"))
      (node (ref "U2") (pin "3") (pinfunction "GND_3") (pintype "passive"))
      (node (ref "U3") (pin "3") (pinfunction "GND_3") (pintype "passive"))
      (node (ref "U3") (pin "6") (pinfunction "EPAD_6") (pintype "passive"))
      (node (ref "U4") (pin "3") (pinfunction "3_3") (pintype "passive"))
      (node (ref "U5") (pin "3") (pinfunction "3_3") (pintype "passive"))
      (node (ref "U6") (pin "3") (pinfunction "3_3") (pintype "passive"))
      (node (ref "U7") (pin "3") (pinfunction "3_3") (pintype "passive"))
      (node (ref "Z1") (pin "1") (pinfunction "1_1") (pintype "passive"))
      (node (ref "Z2") (pin "1") (pinfunction "1_1") (pintype "passive"))
    )
    (net (code "62") (name "Net-(C11-Pad2)") (class "Default")
      (node (ref "C11") (pin "2") (pinfunction "2_2") (pintype "passive"))
      (node (ref "JP1") (pin "1") (pinfunction "1_1") (pintype "passive"))
    )
    (net (code "63") (name "Net-(D1-Anode)") (class "Default")
      (node (ref "D1") (pin "2") (pinfunction "Anode_2") (pintype "passive"))
      (node (ref "R17") (pin "1") (pinfunction "1_1") (pintype "passive"))
    )
    (net (code "64") (name "Net-(D2-Anode)") (class "Default")
      (node (ref "D2") (pin "2") (pinfunction "Anode_2") (pintype "passive"))
      (node (ref "R15") (pin "1") (pinfunction "1_1") (pintype "passive"))
    )
    (net (code "65") (name "Net-(D2-Cathode)") (class "Default")
      (node (ref "D2") (pin "1") (pinfunction "Cathode_1") (pintype "passive"))
      (node (ref "U4") (pin "4") (pinfunction "4_4") (pintype "passive"))
    )
    (net (code "66") (name "Net-(D3-Anode)") (class "Default")
      (node (ref "D3") (pin "2") (pinfunction "Anode_2") (pintype "passive"))
      (node (ref "R2") (pin "1") (pinfunction "1_1") (pintype "passive"))
    )
    (net (code "67") (name "Net-(D4-Anode)") (class "Default")
      (node (ref "D4") (pin "2") (pinfunction "Anode_2") (pintype "passive"))
      (node (ref "R3") (pin "1") (pinfunction "1_1") (pintype "passive"))
    )
    (net (code "68") (name "Net-(D5-Anode)") (class "Default")
      (node (ref "D5") (pin "2") (pinfunction "Anode_2") (pintype "passive"))
      (node (ref "R19") (pin "1") (pinfunction "1_1") (pintype "passive"))
      (node (ref "R23") (pin "1") (pinfunction "1_1") (pintype "passive"))
    )
    (net (code "69") (name "Net-(J7-Pad4)") (class "Default")
      (node (ref "J7") (pin "4") (pinfunction "4_4") (pintype "passive"))
      (node (ref "R8") (pin "2") (pinfunction "2_2") (pintype "passive"))
    )
    (net (code "70") (name "Net-(JP1-Pad3)") (class "Default")
      (node (ref "JP1") (pin "3") (pinfunction "3_3") (pintype "passive"))
      (node (ref "R12") (pin "2") (pinfunction "2_2") (pintype "passive"))
    )
    (net (code "71") (name "Net-(R22-Pad1)") (class "Default")
      (node (ref "R22") (pin "1") (pinfunction "1_1") (pintype "passive"))
      (node (ref "U7") (pin "4") (pinfunction "4_4") (pintype "passive"))
    )
    (net (code "72") (name "unconnected-(J1-Pad1)") (class "Default")
      (node (ref "J1") (pin "1") (pinfunction "1_1") (pintype "passive+no_connect"))
    )
    (net (code "73") (name "unconnected-(J1-Pad8)") (class "Default")
      (node (ref "J1") (pin "8") (pinfunction "8_8") (pintype "passive+no_connect"))
    )
    (net (code "74") (name "unconnected-(MH4-Pad1)") (class "Default")
      (node (ref "MH4") (pin "1") (pinfunction "1_1") (pintype "passive+no_connect"))
    )
    (net (code "75") (name "unconnected-(U2-(AIN0_{slash}_INT1)_PD1-Pad7)") (class "Default")
      (node (ref "U2") (pin "7") (pinfunction "(AIN0_/_INT1)_PD1_7") (pintype "passive+no_connect"))
    )
    (net (code "76") (name "unconnected-(U2-(OC.0B_{slash}_INT0)_PD0-Pad6)") (class "Default")
      (node (ref "U2") (pin "6") (pinfunction "(OC.0B_/_INT0)_PD0_6") (pintype "passive+no_connect"))
    )
    (net (code "77") (name "unconnected-(U2-(PCINT11_{slash}AIN2_)_PC2-Pad5)") (class "Default")
      (node (ref "U2") (pin "5") (pinfunction "(PCINT11_/AIN2_)_PC2_5") (pintype "passive+no_connect"))
    )
    (net (code "78") (name "unconnected-(U2-(SS_{slash}_PCINT0)_PB0-Pad14)") (class "Default")
      (node (ref "U2") (pin "14") (pinfunction "(SS_/_PCINT0)_PB0_14") (pintype "passive+no_connect"))
    )
    (net (code "79") (name "unconnected-(U2-(~{RTS}_{slash}_AIN5_{slash}_INT6)_PD6-Pad12)") (class "Default")
      (node (ref "U2") (pin "12") (pinfunction "(~{RTS}_/_AIN5_/_INT6)_PD6_12") (pintype "passive+no_connect"))
    )
    (net (code "80") (name "unconnected-(U2-PC4_(PCINT10)-Pad26)") (class "Default")
      (node (ref "U2") (pin "26") (pinfunction "PC4_(PCINT10)_26") (pintype "passive+no_connect"))
    )
    (net (code "81") (name "unconnected-(U2-PC5_(_PCINT9{slash}_OC.1B)-Pad25)") (class "Default")
      (node (ref "U2") (pin "25") (pinfunction "PC5_(_PCINT9/_OC.1B)_25") (pintype "passive+no_connect"))
    )
    (net (code "82") (name "unconnected-(U2-PC6_(OC.1A_{slash}_PCINT8)-Pad23)") (class "Default")
      (node (ref "U2") (pin "23") (pinfunction "PC6_(OC.1A_/_PCINT8)_23") (pintype "passive+no_connect"))
    )
    (net (code "83") (name "unconnected-(U2-PC7_(INT4_{slash}_ICP1_{slash}_CLKO)-Pad22)") (class "Default")
      (node (ref "U2") (pin "22") (pinfunction "PC7_(INT4_/_ICP1_/_CLKO)_22") (pintype "passive+no_connect"))
    )
  )
)
